# IOIO_Sensors_Unrouted.net
KiCad netlist of a schematic drawn in EAGLE
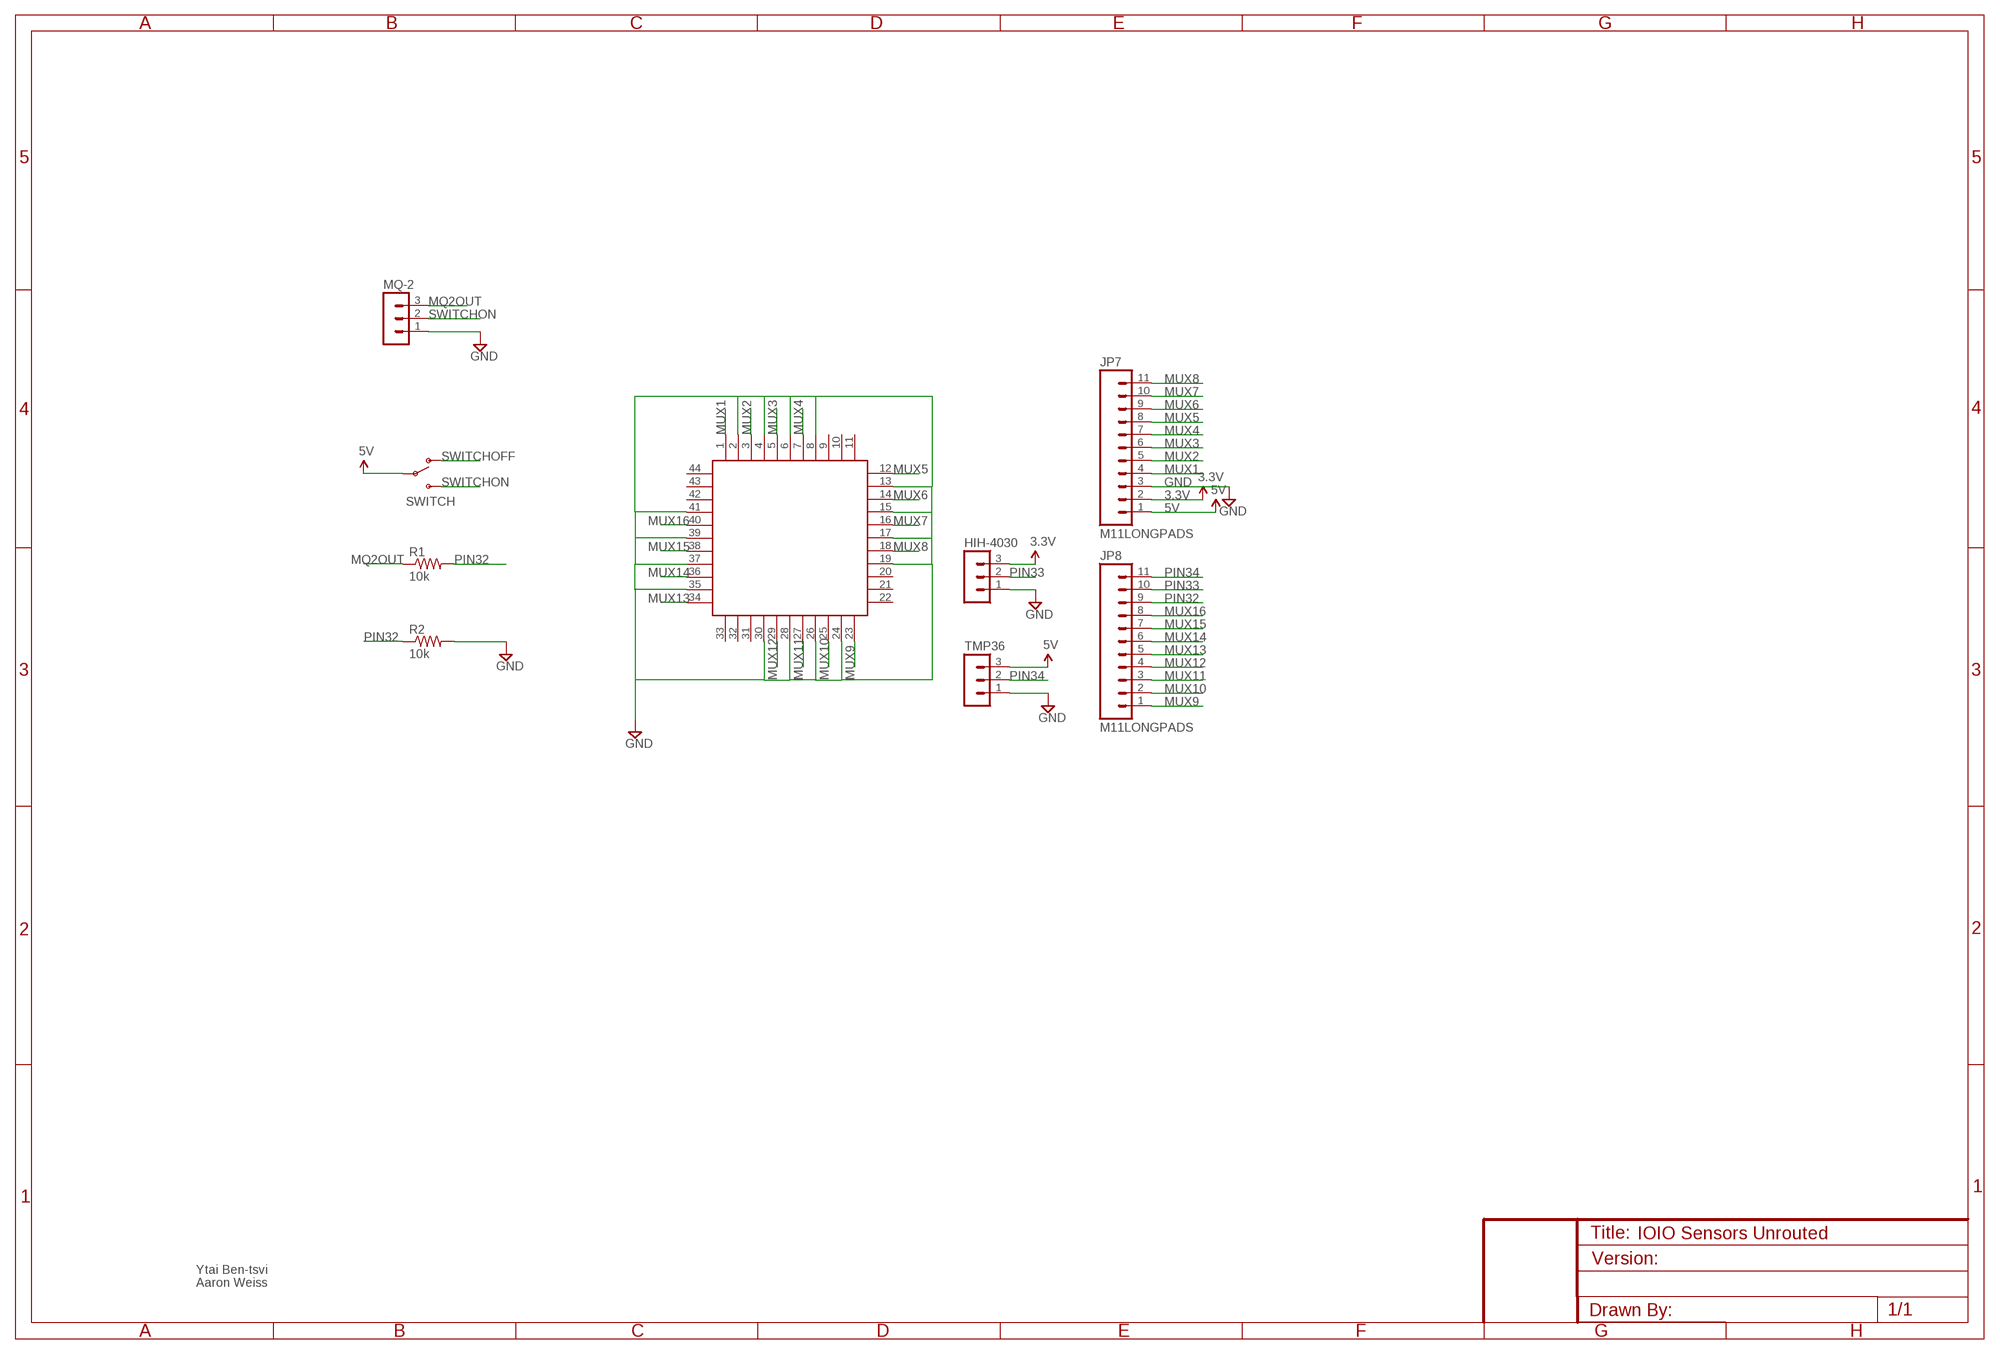
[diagram p0: schematic, sheet 1]

(export (version "E")
  (design (tool "Eeschema 10.0.6"))
  (components
    (comp (ref "HIH-4030")
      (value "MA03-1")
      (footprint "eagle-import:MA03-1")
      (libsource (lib "eagle-import") (part "MA03-1"))
    )
    (comp (ref "JP7")
      (value "M11LONGPADS")
      (footprint "eagle-import:1X11_LONGPADS")
      (libsource (lib "eagle-import") (part "M11LONGPADS"))
    )
    (comp (ref "JP8")
      (value "M11LONGPADS")
      (footprint "eagle-import:1X11_LONGPADS")
      (libsource (lib "eagle-import") (part "M11LONGPADS"))
    )
    (comp (ref "MQ-2")
      (value "MA03-1")
      (footprint "eagle-import:MA03-1")
      (libsource (lib "eagle-import") (part "MA03-1"))
    )
    (comp (ref "R1")
      (value "10k")
      (footprint "eagle-import:0207_7")
      (libsource (lib "eagle-import") (part "R-US_0207/7"))
    )
    (comp (ref "R2")
      (value "10k")
      (footprint "eagle-import:0207_7")
      (libsource (lib "eagle-import") (part "R-US_0207/7"))
    )
    (comp (ref "SWITCH")
      (value "SWITCH-SPSTPTH_LOCK")
      (footprint "eagle-import:SWITCH-SPDT_LOCK.007S")
      (libsource (lib "eagle-import") (part "SWITCH-SPSTPTH_LOCK"))
    )
    (comp (ref "TMP36")
      (value "MA03-1")
      (footprint "eagle-import:MA03-1")
      (libsource (lib "eagle-import") (part "MA03-1"))
    )
    (comp (ref "U$4")
      (value "S44")
      (footprint "eagle-import:S44")
      (libsource (lib "eagle-import") (part "S44"))
    )
  )
  (nets
    (net (code "1") (name "/MQ2OUT") (class "Default")
      (node (ref "MQ-2") (pin "3") (pinfunction "3_3") (pintype "passive"))
      (node (ref "R1") (pin "1") (pinfunction "1_1") (pintype "passive"))
    )
    (net (code "2") (name "/MUX1") (class "Default")
      (node (ref "JP7") (pin "4") (pinfunction "4_4") (pintype "passive"))
      (node (ref "U$4") (pin "1") (pinfunction "P$1_1") (pintype "bidirectional"))
    )
    (net (code "3") (name "/MUX2") (class "Default")
      (node (ref "JP7") (pin "5") (pinfunction "5_5") (pintype "passive"))
      (node (ref "U$4") (pin "3") (pinfunction "P$3_3") (pintype "bidirectional"))
    )
    (net (code "4") (name "/MUX3") (class "Default")
      (node (ref "JP7") (pin "6") (pinfunction "6_6") (pintype "passive"))
      (node (ref "U$4") (pin "5") (pinfunction "P$5_5") (pintype "bidirectional"))
    )
    (net (code "5") (name "/MUX4") (class "Default")
      (node (ref "JP7") (pin "7") (pinfunction "7_7") (pintype "passive"))
      (node (ref "U$4") (pin "7") (pinfunction "P$7_7") (pintype "bidirectional"))
    )
    (net (code "6") (name "/MUX5") (class "Default")
      (node (ref "JP7") (pin "8") (pinfunction "8_8") (pintype "passive"))
      (node (ref "U$4") (pin "12") (pinfunction "P$12_12") (pintype "bidirectional"))
    )
    (net (code "7") (name "/MUX6") (class "Default")
      (node (ref "JP7") (pin "9") (pinfunction "9_9") (pintype "passive"))
      (node (ref "U$4") (pin "14") (pinfunction "P$14_14") (pintype "bidirectional"))
    )
    (net (code "8") (name "/MUX7") (class "Default")
      (node (ref "JP7") (pin "10") (pinfunction "10_10") (pintype "passive"))
      (node (ref "U$4") (pin "16") (pinfunction "P$16_16") (pintype "bidirectional"))
    )
    (net (code "9") (name "/MUX8") (class "Default")
      (node (ref "JP7") (pin "11") (pinfunction "11_11") (pintype "passive"))
      (node (ref "U$4") (pin "18") (pinfunction "P$18_18") (pintype "bidirectional"))
    )
    (net (code "10") (name "/MUX9") (class "Default")
      (node (ref "JP8") (pin "1") (pinfunction "1_1") (pintype "passive"))
      (node (ref "U$4") (pin "23") (pinfunction "P$23_23") (pintype "bidirectional"))
    )
    (net (code "11") (name "/MUX10") (class "Default")
      (node (ref "JP8") (pin "2") (pinfunction "2_2") (pintype "passive"))
      (node (ref "U$4") (pin "25") (pinfunction "P$25_25") (pintype "bidirectional"))
    )
    (net (code "12") (name "/MUX11") (class "Default")
      (node (ref "JP8") (pin "3") (pinfunction "3_3") (pintype "passive"))
      (node (ref "U$4") (pin "27") (pinfunction "P$27_27") (pintype "bidirectional"))
    )
    (net (code "13") (name "/MUX12") (class "Default")
      (node (ref "JP8") (pin "4") (pinfunction "4_4") (pintype "passive"))
      (node (ref "U$4") (pin "29") (pinfunction "P$29_29") (pintype "bidirectional"))
    )
    (net (code "14") (name "/MUX13") (class "Default")
      (node (ref "JP8") (pin "5") (pinfunction "5_5") (pintype "passive"))
      (node (ref "U$4") (pin "34") (pinfunction "P$34_34") (pintype "bidirectional"))
    )
    (net (code "15") (name "/MUX14") (class "Default")
      (node (ref "JP8") (pin "6") (pinfunction "6_6") (pintype "passive"))
      (node (ref "U$4") (pin "36") (pinfunction "P$36_36") (pintype "bidirectional"))
    )
    (net (code "16") (name "/MUX15") (class "Default")
      (node (ref "JP8") (pin "7") (pinfunction "7_7") (pintype "passive"))
      (node (ref "U$4") (pin "38") (pinfunction "P$38_38") (pintype "bidirectional"))
    )
    (net (code "17") (name "/MUX16") (class "Default")
      (node (ref "JP8") (pin "8") (pinfunction "8_8") (pintype "passive"))
      (node (ref "U$4") (pin "40") (pinfunction "P$40_40") (pintype "bidirectional"))
    )
    (net (code "18") (name "/PIN32") (class "Default")
      (node (ref "JP8") (pin "9") (pinfunction "9_9") (pintype "passive"))
      (node (ref "R1") (pin "2") (pinfunction "2_2") (pintype "passive"))
      (node (ref "R2") (pin "1") (pinfunction "1_1") (pintype "passive"))
    )
    (net (code "19") (name "/PIN33") (class "Default")
      (node (ref "HIH-4030") (pin "2") (pinfunction "2_2") (pintype "passive"))
      (node (ref "JP8") (pin "10") (pinfunction "10_10") (pintype "passive"))
    )
    (net (code "20") (name "/PIN34") (class "Default")
      (node (ref "JP8") (pin "11") (pinfunction "11_11") (pintype "passive"))
      (node (ref "TMP36") (pin "2") (pinfunction "2_2") (pintype "passive"))
    )
    (net (code "21") (name "/SWITCHOFF") (class "Default")
      (node (ref "SWITCH") (pin "1") (pinfunction "O_1") (pintype "passive"))
    )
    (net (code "22") (name "/SWITCHON") (class "Default")
      (node (ref "MQ-2") (pin "2") (pinfunction "2_2") (pintype "passive"))
      (node (ref "SWITCH") (pin "3") (pinfunction "S_3") (pintype "passive"))
    )
    (net (code "23") (name "3.3V") (class "Default")
      (node (ref "HIH-4030") (pin "3") (pinfunction "3_3") (pintype "passive"))
      (node (ref "JP7") (pin "2") (pinfunction "2_2") (pintype "passive"))
    )
    (net (code "24") (name "5V") (class "Default")
      (node (ref "JP7") (pin "1") (pinfunction "1_1") (pintype "passive"))
      (node (ref "SWITCH") (pin "2") (pinfunction "P_2") (pintype "passive"))
      (node (ref "TMP36") (pin "3") (pinfunction "3_3") (pintype "passive"))
    )
    (net (code "25") (name "GND") (class "Default")
      (node (ref "HIH-4030") (pin "1") (pinfunction "1_1") (pintype "passive"))
      (node (ref "JP7") (pin "3") (pinfunction "3_3") (pintype "passive"))
      (node (ref "MQ-2") (pin "1") (pinfunction "1_1") (pintype "passive"))
      (node (ref "R2") (pin "2") (pinfunction "2_2") (pintype "passive"))
      (node (ref "TMP36") (pin "1") (pinfunction "1_1") (pintype "passive"))
      (node (ref "U$4") (pin "13") (pinfunction "P$13_13") (pintype "bidirectional"))
      (node (ref "U$4") (pin "15") (pinfunction "P$15_15") (pintype "bidirectional"))
      (node (ref "U$4") (pin "17") (pinfunction "P$17_17") (pintype "bidirectional"))
      (node (ref "U$4") (pin "19") (pinfunction "P$19_19") (pintype "bidirectional"))
      (node (ref "U$4") (pin "2") (pinfunction "P$2_2") (pintype "bidirectional"))
      (node (ref "U$4") (pin "24") (pinfunction "P$24_24") (pintype "bidirectional"))
      (node (ref "U$4") (pin "26") (pinfunction "P$26_26") (pintype "bidirectional"))
      (node (ref "U$4") (pin "28") (pinfunction "P$28_28") (pintype "bidirectional"))
      (node (ref "U$4") (pin "30") (pinfunction "P$30_30") (pintype "bidirectional"))
      (node (ref "U$4") (pin "35") (pinfunction "P$35_35") (pintype "bidirectional"))
      (node (ref "U$4") (pin "37") (pinfunction "P$37_37") (pintype "bidirectional"))
      (node (ref "U$4") (pin "39") (pinfunction "P$39_39") (pintype "bidirectional"))
      (node (ref "U$4") (pin "4") (pinfunction "P$4_4") (pintype "bidirectional"))
      (node (ref "U$4") (pin "41") (pinfunction "P$41_41") (pintype "bidirectional"))
      (node (ref "U$4") (pin "6") (pinfunction "P$6_6") (pintype "bidirectional"))
      (node (ref "U$4") (pin "8") (pinfunction "P$8_8") (pintype "bidirectional"))
    )
    (net (code "26") (name "unconnected-(U$4-P$9-Pad9)") (class "Default")
      (node (ref "U$4") (pin "9") (pinfunction "P$9_9") (pintype "bidirectional"))
    )
    (net (code "27") (name "unconnected-(U$4-P$10-Pad10)") (class "Default")
      (node (ref "U$4") (pin "10") (pinfunction "P$10_10") (pintype "bidirectional"))
    )
    (net (code "28") (name "unconnected-(U$4-P$11-Pad11)") (class "Default")
      (node (ref "U$4") (pin "11") (pinfunction "P$11_11") (pintype "bidirectional"))
    )
    (net (code "29") (name "unconnected-(U$4-P$20-Pad20)") (class "Default")
      (node (ref "U$4") (pin "20") (pinfunction "P$20_20") (pintype "bidirectional"))
    )
    (net (code "30") (name "unconnected-(U$4-P$21-Pad21)") (class "Default")
      (node (ref "U$4") (pin "21") (pinfunction "P$21_21") (pintype "bidirectional"))
    )
    (net (code "31") (name "unconnected-(U$4-P$22-Pad22)") (class "Default")
      (node (ref "U$4") (pin "22") (pinfunction "P$22_22") (pintype "bidirectional"))
    )
    (net (code "32") (name "unconnected-(U$4-P$31-Pad31)") (class "Default")
      (node (ref "U$4") (pin "31") (pinfunction "P$31_31") (pintype "bidirectional"))
    )
    (net (code "33") (name "unconnected-(U$4-P$32-Pad32)") (class "Default")
      (node (ref "U$4") (pin "32") (pinfunction "P$32_32") (pintype "bidirectional"))
    )
    (net (code "34") (name "unconnected-(U$4-P$33-Pad33)") (class "Default")
      (node (ref "U$4") (pin "33") (pinfunction "P$33_33") (pintype "bidirectional"))
    )
    (net (code "35") (name "unconnected-(U$4-P$42-Pad42)") (class "Default")
      (node (ref "U$4") (pin "42") (pinfunction "P$42_42") (pintype "bidirectional"))
    )
    (net (code "36") (name "unconnected-(U$4-P$43-Pad43)") (class "Default")
      (node (ref "U$4") (pin "43") (pinfunction "P$43_43") (pintype "bidirectional"))
    )
    (net (code "37") (name "unconnected-(U$4-P$44-Pad44)") (class "Default")
      (node (ref "U$4") (pin "44") (pinfunction "P$44_44") (pintype "bidirectional"))
    )
  )
)
